# Monoblink.net
KiCad netlist of a schematic drawn in EAGLE
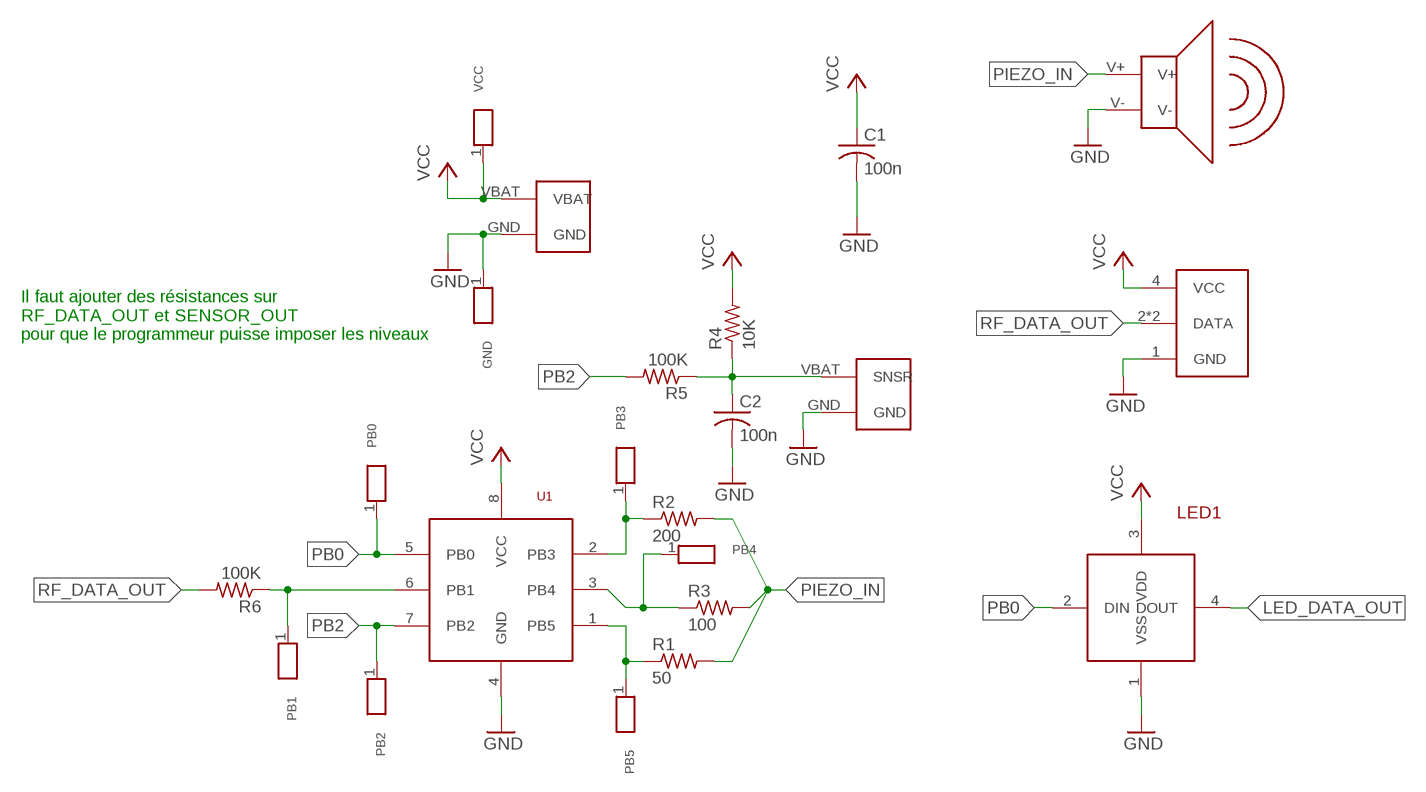
[diagram p0: schematic, sheet 1]

(export (version "E")
  (design (tool "Eeschema 10.0.6"))
  (components
    (comp (ref "C1")
      (value "100n")
      (footprint "eagle-import:C0603")
      (libsource (lib "eagle-import") (part "C-USC0603"))
    )
    (comp (ref "C2")
      (value "100n")
      (footprint "eagle-import:C0603")
      (libsource (lib "eagle-import") (part "C-USC0603"))
    )
    (comp (ref "GND")
      (value "TESTPAD_PROG_BOARD")
      (footprint "eagle-import:TP2MM")
      (libsource (lib "eagle-import") (part "TESTPAD_PROG_BOARD"))
    )
    (comp (ref "LED1")
      (value "NEOPIXEL")
      (footprint "eagle-import:SMD5050")
      (libsource (lib "eagle-import") (part "NEOPIXEL"))
    )
    (comp (ref "PB0")
      (value "TESTPAD_PROG_BOARD")
      (footprint "eagle-import:TP2MM")
      (libsource (lib "eagle-import") (part "TESTPAD_PROG_BOARD"))
    )
    (comp (ref "PB1")
      (value "TESTPAD_PROG_BOARD")
      (footprint "eagle-import:TP2MM")
      (libsource (lib "eagle-import") (part "TESTPAD_PROG_BOARD"))
    )
    (comp (ref "PB2")
      (value "TESTPAD_PROG_BOARD")
      (footprint "eagle-import:TP2MM")
      (libsource (lib "eagle-import") (part "TESTPAD_PROG_BOARD"))
    )
    (comp (ref "PB3")
      (value "TESTPAD_PROG_BOARD")
      (footprint "eagle-import:TP2MM")
      (libsource (lib "eagle-import") (part "TESTPAD_PROG_BOARD"))
    )
    (comp (ref "PB4")
      (value "TESTPAD_PROG_BOARD")
      (footprint "eagle-import:TP2MM")
      (libsource (lib "eagle-import") (part "TESTPAD_PROG_BOARD"))
    )
    (comp (ref "PB5")
      (value "TESTPAD_PROG_BOARD")
      (footprint "eagle-import:TP2MM")
      (libsource (lib "eagle-import") (part "TESTPAD_PROG_BOARD"))
    )
    (comp (ref "R1")
      (value "50")
      (footprint "eagle-import:R0603")
      (libsource (lib "eagle-import") (part "R-US_R0603"))
    )
    (comp (ref "R2")
      (value "200")
      (footprint "eagle-import:R0603")
      (libsource (lib "eagle-import") (part "R-US_R0603"))
    )
    (comp (ref "R3")
      (value "100")
      (footprint "eagle-import:R0603")
      (libsource (lib "eagle-import") (part "R-US_R0603"))
    )
    (comp (ref "R4")
      (value "10K")
      (footprint "eagle-import:R0603")
      (libsource (lib "eagle-import") (part "R-US_R0603"))
    )
    (comp (ref "R5")
      (value "100K")
      (footprint "eagle-import:R0603")
      (libsource (lib "eagle-import") (part "R-US_R0603"))
    )
    (comp (ref "R6")
      (value "100K")
      (footprint "eagle-import:R0603")
      (libsource (lib "eagle-import") (part "R-US_R0603"))
    )
    (comp (ref "U$1")
      (value "RF_CONN")
      (footprint "eagle-import:RF_CONN")
      (libsource (lib "eagle-import") (part "RF_CONN"))
    )
    (comp (ref "U$2")
      (value "PIEZO")
      (footprint "eagle-import:PS1240P02BT")
      (libsource (lib "eagle-import") (part "PIEZO"))
    )
    (comp (ref "U$3")
      (value "BATT_TH")
      (footprint "eagle-import:TWO_TH")
      (libsource (lib "eagle-import") (part "BATT_TH"))
    )
    (comp (ref "U$4")
      (value "SNSR_CONN")
      (footprint "eagle-import:TWO_TH")
      (libsource (lib "eagle-import") (part "SNSR_CONN"))
    )
    (comp (ref "U1")
      (value "ATTINY85")
      (footprint "eagle-import:SOIC8")
      (libsource (lib "eagle-import") (part "ATTINY85"))
    )
    (comp (ref "VCC")
      (value "TESTPAD_PROG_BOARD")
      (footprint "eagle-import:TP2MM")
      (libsource (lib "eagle-import") (part "TESTPAD_PROG_BOARD"))
    )
  )
  (nets
    (net (code "1") (name "GND") (class "Default")
      (node (ref "C1") (pin "2") (pinfunction "2_2") (pintype "passive"))
      (node (ref "C2") (pin "2") (pinfunction "2_2") (pintype "passive"))
      (node (ref "GND") (pin "1") (pinfunction "1_1") (pintype "bidirectional"))
      (node (ref "LED1") (pin "1") (pinfunction "VSS_1") (pintype "bidirectional"))
      (node (ref "U$1") (pin "1") (pinfunction "GND_1") (pintype "bidirectional"))
      (node (ref "U$2") (pin "V-") (pinfunction "V-_V-") (pintype "bidirectional"))
      (node (ref "U$3") (pin "GND") (pinfunction "GND_GND") (pintype "bidirectional"))
      (node (ref "U$4") (pin "GND") (pinfunction "GND_GND") (pintype "bidirectional"))
      (node (ref "U1") (pin "4") (pinfunction "GND_4") (pintype "bidirectional"))
    )
    (net (code "2") (name "LED_DATA_OUT") (class "Default")
      (node (ref "LED1") (pin "4") (pinfunction "DOUT_4") (pintype "bidirectional"))
    )
    (net (code "3") (name "Net-(U$4-SNSR)") (class "Default")
      (node (ref "C2") (pin "1") (pinfunction "1_1") (pintype "passive"))
      (node (ref "R4") (pin "1") (pinfunction "1_1") (pintype "passive"))
      (node (ref "R5") (pin "1") (pinfunction "1_1") (pintype "passive"))
      (node (ref "U$4") (pin "VBAT") (pinfunction "SNSR_VBAT") (pintype "bidirectional"))
    )
    (net (code "4") (name "Net-(U1-PB1)") (class "Default")
      (node (ref "PB1") (pin "1") (pinfunction "1_1") (pintype "bidirectional"))
      (node (ref "R6") (pin "1") (pinfunction "1_1") (pintype "passive"))
      (node (ref "U1") (pin "6") (pinfunction "PB1_6") (pintype "bidirectional"))
    )
    (net (code "5") (name "Net-(U1-PB3)") (class "Default")
      (node (ref "PB3") (pin "1") (pinfunction "1_1") (pintype "bidirectional"))
      (node (ref "R2") (pin "1") (pinfunction "1_1") (pintype "passive"))
      (node (ref "U1") (pin "2") (pinfunction "PB3_2") (pintype "bidirectional"))
    )
    (net (code "6") (name "Net-(U1-PB4)") (class "Default")
      (node (ref "PB4") (pin "1") (pinfunction "1_1") (pintype "bidirectional"))
      (node (ref "R3") (pin "1") (pinfunction "1_1") (pintype "passive"))
      (node (ref "U1") (pin "3") (pinfunction "PB4_3") (pintype "bidirectional"))
    )
    (net (code "7") (name "Net-(U1-PB5)") (class "Default")
      (node (ref "PB5") (pin "1") (pinfunction "1_1") (pintype "bidirectional"))
      (node (ref "R1") (pin "1") (pinfunction "1_1") (pintype "passive"))
      (node (ref "U1") (pin "1") (pinfunction "PB5_1") (pintype "bidirectional"))
    )
    (net (code "8") (name "PB0") (class "Default")
      (node (ref "LED1") (pin "2") (pinfunction "DIN_2") (pintype "bidirectional"))
      (node (ref "PB0") (pin "1") (pinfunction "1_1") (pintype "bidirectional"))
      (node (ref "U1") (pin "5") (pinfunction "PB0_5") (pintype "bidirectional"))
    )
    (net (code "9") (name "PB2") (class "Default")
      (node (ref "PB2") (pin "1") (pinfunction "1_1") (pintype "bidirectional"))
      (node (ref "R5") (pin "2") (pinfunction "2_2") (pintype "passive"))
      (node (ref "U1") (pin "7") (pinfunction "PB2_7") (pintype "bidirectional"))
    )
    (net (code "10") (name "PIEZO_IN") (class "Default")
      (node (ref "R1") (pin "2") (pinfunction "2_2") (pintype "passive"))
      (node (ref "R2") (pin "2") (pinfunction "2_2") (pintype "passive"))
      (node (ref "R3") (pin "2") (pinfunction "2_2") (pintype "passive"))
      (node (ref "U$2") (pin "V+") (pinfunction "V+_V+") (pintype "bidirectional"))
    )
    (net (code "11") (name "RF_DATA_OUT") (class "Default")
      (node (ref "R6") (pin "2") (pinfunction "2_2") (pintype "passive"))
      (node (ref "U$1") (pin "2") (pinfunction "DATA_2") (pintype "bidirectional"))
      (node (ref "U$1") (pin "3") (pinfunction "DATA_3") (pintype "bidirectional"))
    )
    (net (code "12") (name "VCC") (class "Default")
      (node (ref "C1") (pin "1") (pinfunction "1_1") (pintype "passive"))
      (node (ref "LED1") (pin "3") (pinfunction "VDD_3") (pintype "bidirectional"))
      (node (ref "R4") (pin "2") (pinfunction "2_2") (pintype "passive"))
      (node (ref "U$1") (pin "4") (pinfunction "VCC_4") (pintype "bidirectional"))
      (node (ref "U$3") (pin "VBAT") (pinfunction "VBAT_VBAT") (pintype "bidirectional"))
      (node (ref "U1") (pin "8") (pinfunction "VCC_8") (pintype "bidirectional"))
      (node (ref "VCC") (pin "1") (pinfunction "1_1") (pintype "bidirectional"))
    )
  )
)
